# ultra.net
KiCad netlist of a schematic drawn in Altium Designer
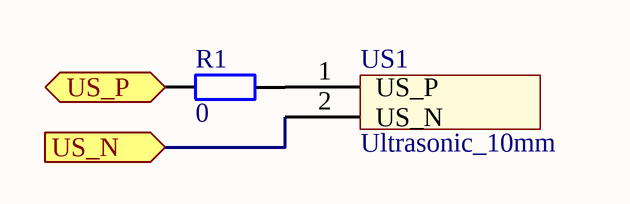
[diagram p0: ultra.SchDoc]

(export (version "E")
  (design (tool "Eeschema 10.0.6"))
  (components
    (comp (ref "R1")
      (value "0")
      (footprint "R-0603-M")
      (description "Resistor 0")
      (libsource (lib "Passives") (part "R-0603-0"))
    )
    (comp (ref "US1")
      (value "Ultrasonic_10mm")
      (footprint "ULTRA_10")
      (libsource (lib "advanced") (part "Ultrasonic_10mm"))
    )
  )
  (nets
    (net (code "1") (name "/US_N") (class "Default")
      (node (ref "US1") (pin "2") (pinfunction "US_N_2") (pintype "passive"))
    )
    (net (code "2") (name "/US_P") (class "Default")
      (node (ref "R1") (pin "1") (pinfunction "1_1") (pintype "passive"))
    )
    (net (code "3") (name "Net-(US1-US_P)") (class "Default")
      (node (ref "R1") (pin "2") (pinfunction "2_2") (pintype "passive"))
      (node (ref "US1") (pin "1") (pinfunction "US_P_1") (pintype "passive"))
    )
  )
)
